# shematic.net
KiCad netlist of a schematic drawn in EAGLE
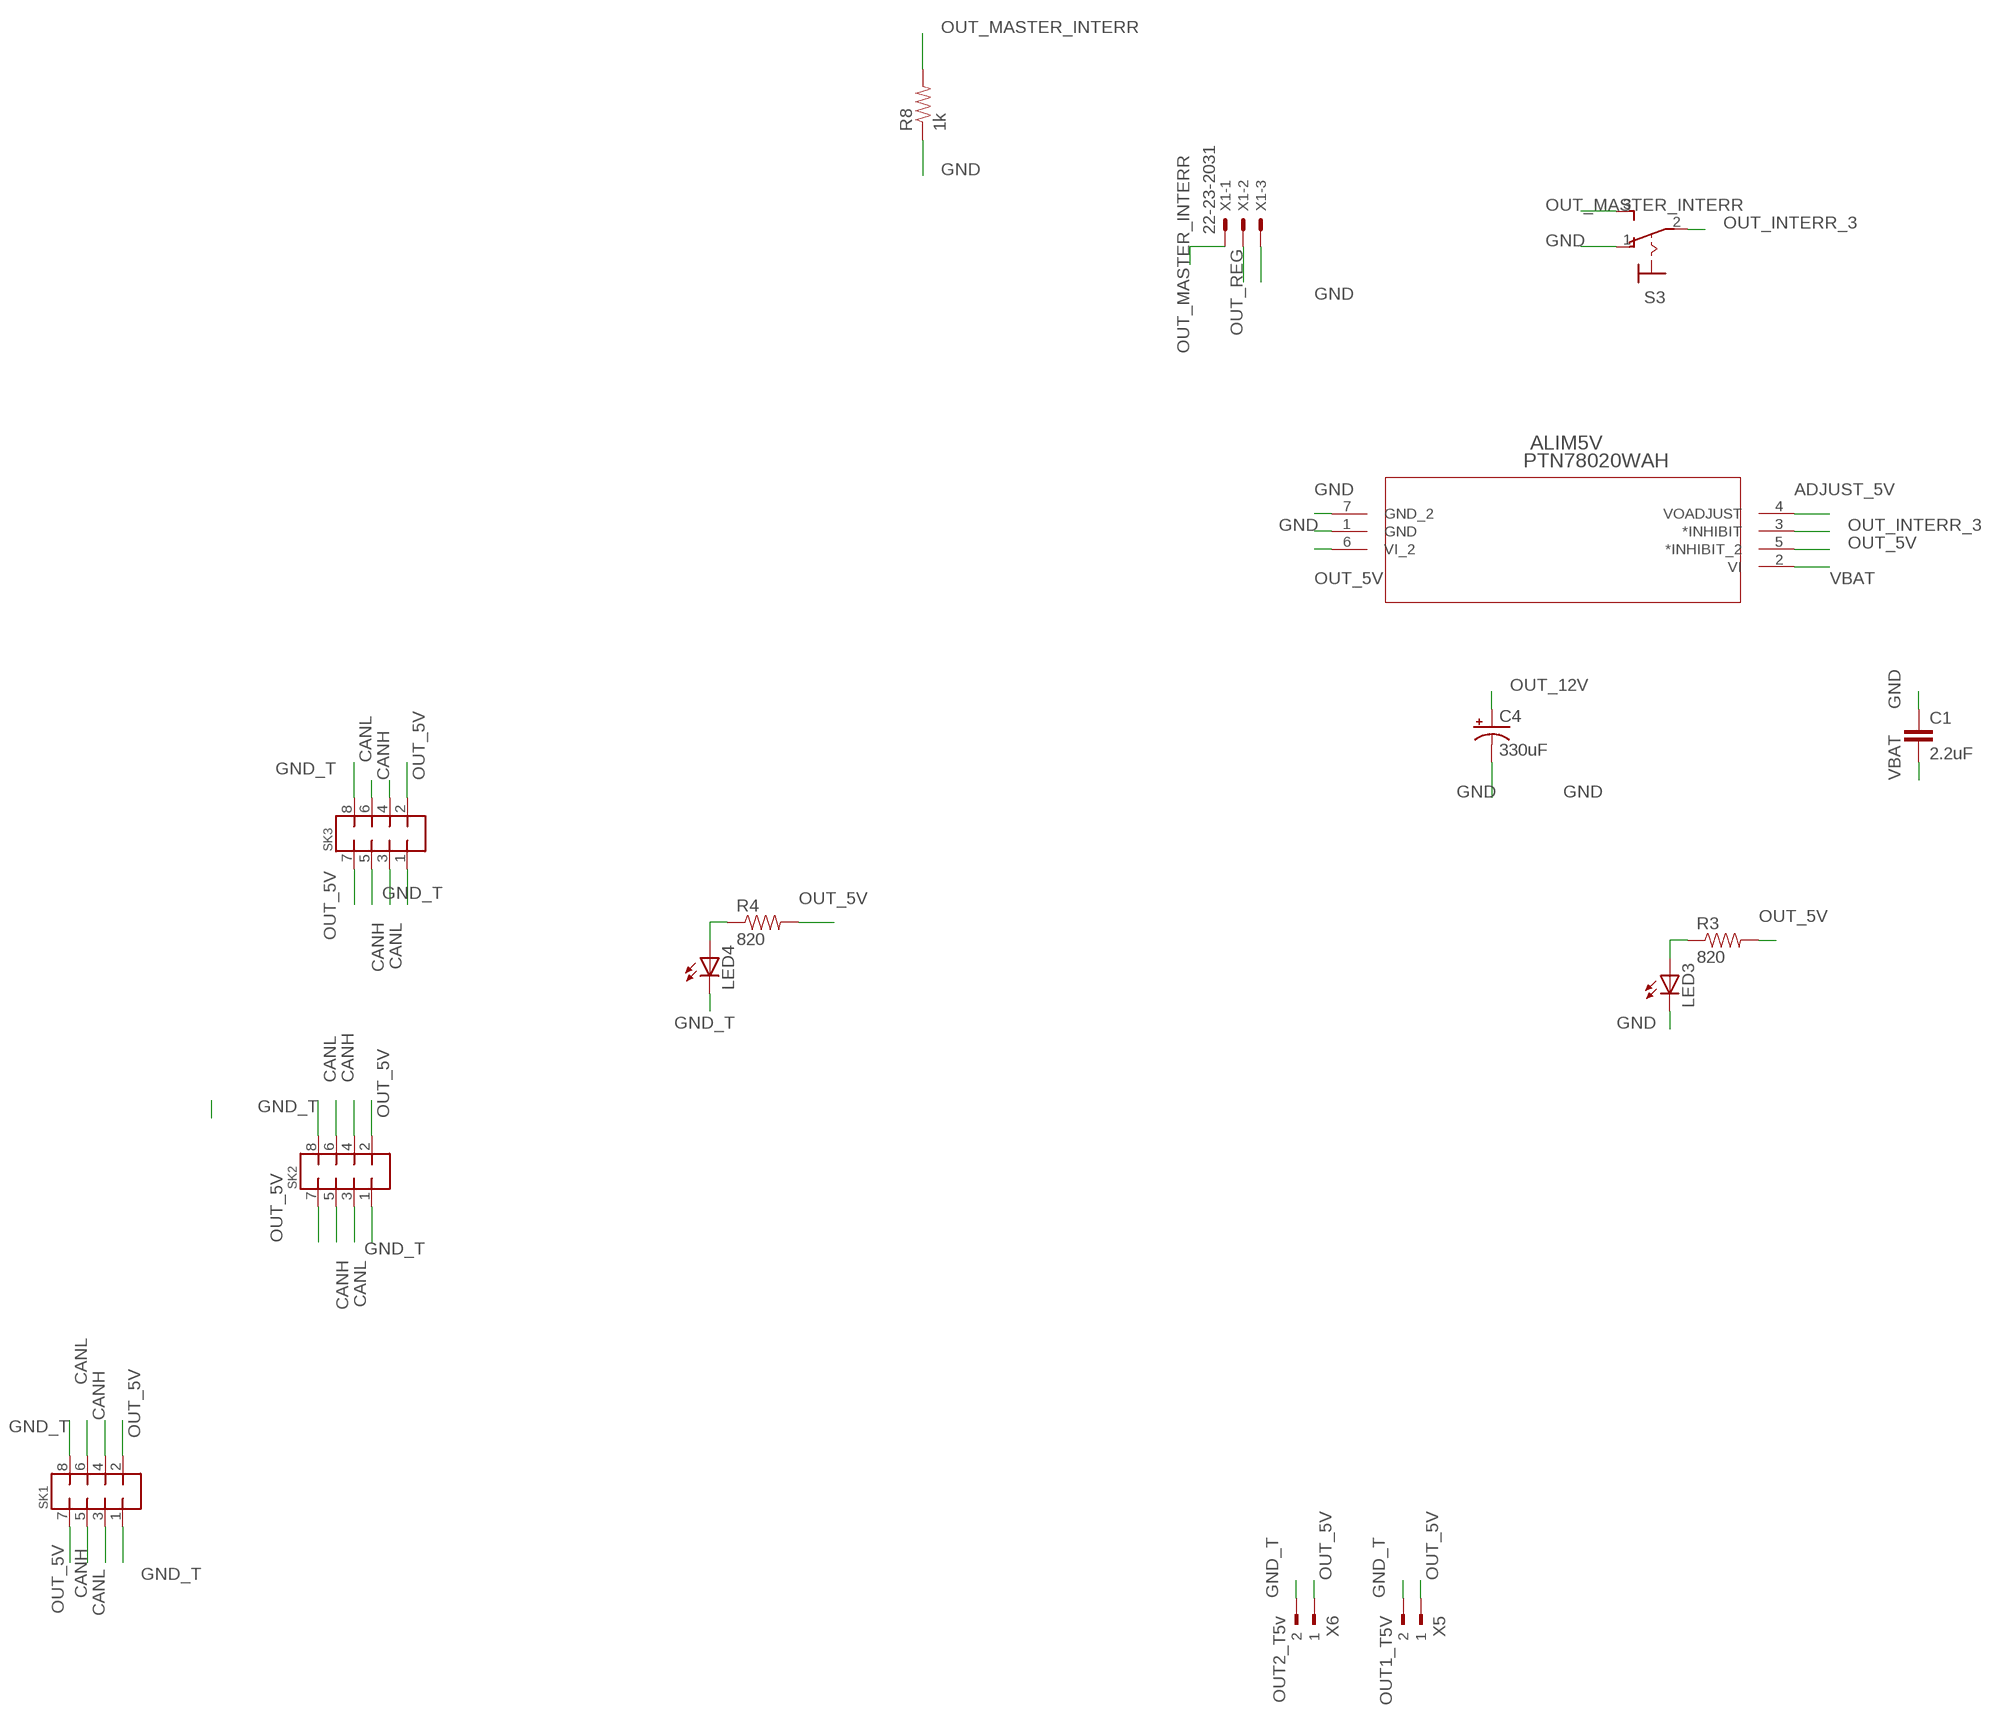
[diagram p0: schematic, sheet 1, part 1 of 2]
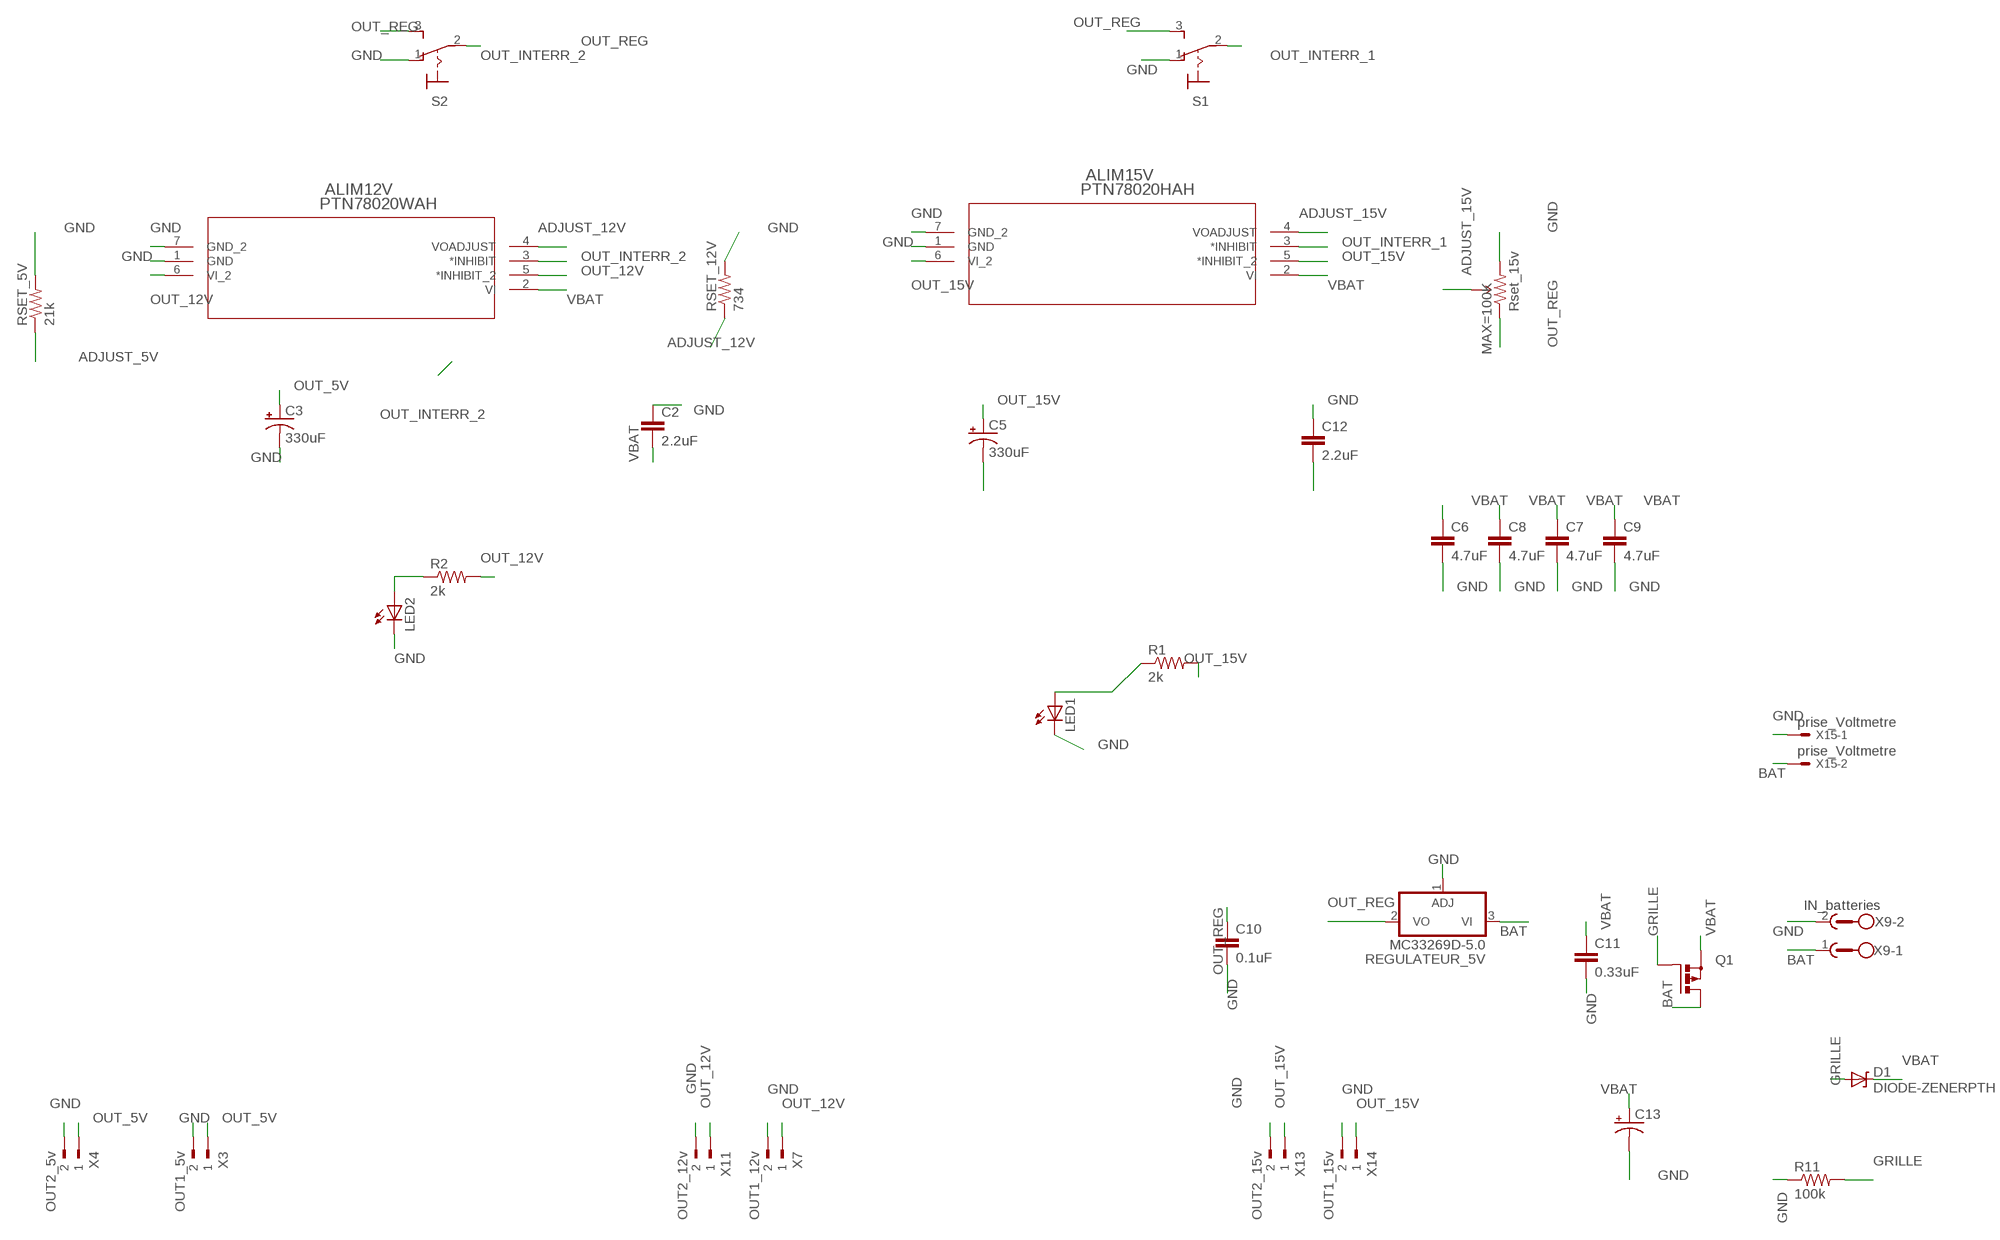
[diagram p1: schematic, sheet 1, part 2 of 2]

(export (version "E")
  (design (tool "Eeschema 10.0.6"))
  (components
    (comp (ref "ALIM5V")
      (value "PTN78020WAH")
      (footprint "eagle-import:EUK7")
      (libsource (lib "eagle-import") (part "PTN78020_"))
    )
    (comp (ref "ALIM12V")
      (value "PTN78020WAH")
      (footprint "eagle-import:EUK7")
      (libsource (lib "eagle-import") (part "PTN78020_"))
    )
    (comp (ref "ALIM15V")
      (value "PTN78020HAH")
      (footprint "eagle-import:EUK7")
      (libsource (lib "eagle-import") (part "PTN78020_"))
    )
    (comp (ref "C1")
      (value "2.2uF")
      (footprint "eagle-import:0805")
      (libsource (lib "eagle-import") (part "CAP0805"))
    )
    (comp (ref "C2")
      (value "2.2uF")
      (footprint "eagle-import:0805")
      (libsource (lib "eagle-import") (part "CAP0805"))
    )
    (comp (ref "C3")
      (value "330uF")
      (footprint "eagle-import:CPOL-RADIAL-100UF-25V")
      (libsource (lib "eagle-import") (part "CAP_POLPTH1"))
    )
    (comp (ref "C4")
      (value "330uF")
      (footprint "eagle-import:CPOL-RADIAL-100UF-25V")
      (libsource (lib "eagle-import") (part "CAP_POLPTH1"))
    )
    (comp (ref "C5")
      (value "330uF")
      (footprint "eagle-import:CPOL-RADIAL-100UF-25V")
      (libsource (lib "eagle-import") (part "CAP_POLPTH1"))
    )
    (comp (ref "C6")
      (value "4.7uF")
      (footprint "eagle-import:0805")
      (libsource (lib "eagle-import") (part "CAP0805"))
    )
    (comp (ref "C7")
      (value "4.7uF")
      (footprint "eagle-import:0805")
      (libsource (lib "eagle-import") (part "CAP0805"))
    )
    (comp (ref "C8")
      (value "4.7uF")
      (footprint "eagle-import:0805")
      (libsource (lib "eagle-import") (part "CAP0805"))
    )
    (comp (ref "C9")
      (value "4.7uF")
      (footprint "eagle-import:0805")
      (libsource (lib "eagle-import") (part "CAP0805"))
    )
    (comp (ref "C10")
      (value "0.1uF")
      (footprint "eagle-import:0805")
      (libsource (lib "eagle-import") (part "CAP0805"))
    )
    (comp (ref "C11")
      (value "0.33uF")
      (footprint "eagle-import:0805")
      (libsource (lib "eagle-import") (part "CAP0805"))
    )
    (comp (ref "C12")
      (value "2.2uF")
      (footprint "eagle-import:0805")
      (libsource (lib "eagle-import") (part "CAP0805"))
    )
    (comp (ref "C13")
      (value "CAP_POLPTH1")
      (footprint "eagle-import:CPOL-RADIAL-100UF-25V")
      (libsource (lib "eagle-import") (part "SparkFun-Passives_CAP_POLPTH1"))
    )
    (comp (ref "D1")
      (value "DIODE-ZENERPTH")
      (footprint "eagle-import:DIODE-ZENER")
      (libsource (lib "eagle-import") (part "DIODE-ZENERPTH"))
    )
    (comp (ref "LED1")
      (value "LEDCHIP-LED0805")
      (footprint "eagle-import:CHIP-LED0805")
      (libsource (lib "eagle-import") (part "LEDCHIP-LED0805"))
    )
    (comp (ref "LED2")
      (value "LEDCHIP-LED0805")
      (footprint "eagle-import:CHIP-LED0805")
      (libsource (lib "eagle-import") (part "LEDCHIP-LED0805"))
    )
    (comp (ref "LED3")
      (value "LEDCHIP-LED0805")
      (footprint "eagle-import:CHIP-LED0805")
      (libsource (lib "eagle-import") (part "LEDCHIP-LED0805"))
    )
    (comp (ref "LED4")
      (value "LEDCHIP-LED0805")
      (footprint "eagle-import:CHIP-LED0805")
      (libsource (lib "eagle-import") (part "LEDCHIP-LED0805"))
    )
    (comp (ref "MAX=100K")
      (value "Rset_15v")
      (footprint "eagle-import:3386U")
      (libsource (lib "eagle-import") (part "TRIMPOT-PTH-KNOB"))
    )
    (comp (ref "Q1")
      (value "PMOSFET_PTO220BH")
      (footprint "eagle-import:TO220BH")
      (libsource (lib "eagle-import") (part "PMOSFET_PTO220BH"))
    )
    (comp (ref "R1")
      (value "2k")
      (footprint "eagle-import:0805")
      (libsource (lib "eagle-import") (part "SparkFun-Resistors_RESISTOR0805-RES"))
    )
    (comp (ref "R2")
      (value "2k")
      (footprint "eagle-import:0805")
      (libsource (lib "eagle-import") (part "SparkFun-Resistors_RESISTOR0805-RES"))
    )
    (comp (ref "R3")
      (value "820")
      (footprint "eagle-import:0805")
      (libsource (lib "eagle-import") (part "SparkFun-Resistors_RESISTOR0805-RES"))
    )
    (comp (ref "R4")
      (value "820")
      (footprint "eagle-import:0805")
      (libsource (lib "eagle-import") (part "SparkFun-Resistors_RESISTOR0805-RES"))
    )
    (comp (ref "R8")
      (value "1k")
      (footprint "eagle-import:0805")
      (libsource (lib "eagle-import") (part "SparkFun-Resistors_RESISTOR0805-RES"))
    )
    (comp (ref "R11")
      (value "100k")
      (footprint "eagle-import:0805")
      (libsource (lib "eagle-import") (part "RESISTOR0805-RES"))
    )
    (comp (ref "REGULATEUR_5V")
      (value "MC33269D-5.0")
      (footprint "eagle-import:DPACK")
      (libsource (lib "eagle-import") (part "MC33269?D-5.0"))
    )
    (comp (ref "RSET_5V")
      (value "21k")
      (footprint "eagle-import:0805")
      (libsource (lib "eagle-import") (part "RESISTOR0805-RES"))
    )
    (comp (ref "RSET_12V")
      (value "734")
      (footprint "eagle-import:0805")
      (libsource (lib "eagle-import") (part "RESISTOR0805-RES"))
    )
    (comp (ref "S1")
      (value "M9040P")
      (footprint "eagle-import:M9040P")
      (libsource (lib "eagle-import") (part "M9040P"))
    )
    (comp (ref "S2")
      (value "M9040P")
      (footprint "eagle-import:M9040P")
      (libsource (lib "eagle-import") (part "M9040P"))
    )
    (comp (ref "S3")
      (value "M9040P")
      (footprint "eagle-import:M9040P")
      (libsource (lib "eagle-import") (part "M9040P"))
    )
    (comp (ref "SK1")
      (value "MMATCH-8-PTH")
      (footprint "eagle-import:AMP-215079-8")
      (libsource (lib "eagle-import") (part "MMATCH-8-PTH"))
    )
    (comp (ref "SK2")
      (value "MMATCH-8-PTH")
      (footprint "eagle-import:AMP-215079-8")
      (libsource (lib "eagle-import") (part "MMATCH-8-PTH"))
    )
    (comp (ref "SK3")
      (value "MMATCH-8-PTH")
      (footprint "eagle-import:AMP-215079-8")
      (libsource (lib "eagle-import") (part "MMATCH-8-PTH"))
    )
    (comp (ref "X1")
      (value "22-23-2031")
      (footprint "eagle-import:22-23-2031")
      (fields (field (name "MF") "MOLEX"))
      (libsource (lib "eagle-import") (part "22-23-2031"))
    )
    (comp (ref "X3")
      (value "OUT1_5v")
      (footprint "eagle-import:90-2")
      (libsource (lib "eagle-import") (part "90-2"))
    )
    (comp (ref "X4")
      (value "OUT2_5v")
      (footprint "eagle-import:90-2")
      (libsource (lib "eagle-import") (part "90-2"))
    )
    (comp (ref "X5")
      (value "OUT1_T5V")
      (footprint "eagle-import:90-2")
      (libsource (lib "eagle-import") (part "90-2"))
    )
    (comp (ref "X6")
      (value "OUT2_T5v")
      (footprint "eagle-import:90-2")
      (libsource (lib "eagle-import") (part "90-2"))
    )
    (comp (ref "X7")
      (value "OUT1_12v")
      (footprint "eagle-import:90-2")
      (libsource (lib "eagle-import") (part "90-2"))
    )
    (comp (ref "X9")
      (value "IN_batteries")
      (footprint "eagle-import:GMSTBA2")
      (fields (field (name "MF") "FARNELL") (field (name "MPN") "1757242"))
      (libsource (lib "eagle-import") (part "GMSTBA2"))
    )
    (comp (ref "X11")
      (value "OUT2_12v")
      (footprint "eagle-import:90-2")
      (libsource (lib "eagle-import") (part "90-2"))
    )
    (comp (ref "X13")
      (value "OUT2_15v")
      (footprint "eagle-import:90-2")
      (libsource (lib "eagle-import") (part "90-2"))
    )
    (comp (ref "X14")
      (value "OUT1_15v")
      (footprint "eagle-import:90-2")
      (libsource (lib "eagle-import") (part "90-2"))
    )
    (comp (ref "X15")
      (value "prise_Voltmetre")
      (footprint "eagle-import:KK-156-2")
      (libsource (lib "eagle-import") (part "KK-156-2"))
    )
  )
  (nets
    (net (code "1") (name "/ADJUST_5V") (class "Default")
      (node (ref "ALIM5V") (pin "4") (pinfunction "VOADJUST_4") (pintype "passive"))
      (node (ref "RSET_5V") (pin "1") (pinfunction "1_1") (pintype "passive"))
    )
    (net (code "2") (name "/ADJUST_12V") (class "Default")
      (node (ref "ALIM12V") (pin "4") (pinfunction "VOADJUST_4") (pintype "passive"))
      (node (ref "RSET_12V") (pin "1") (pinfunction "1_1") (pintype "passive"))
    )
    (net (code "3") (name "/ADJUST_15V") (class "Default")
      (node (ref "ALIM15V") (pin "4") (pinfunction "VOADJUST_4") (pintype "passive"))
      (node (ref "MAX=100K") (pin "2") (pinfunction "WIPER_2") (pintype "passive"))
    )
    (net (code "4") (name "/BAT") (class "Default")
      (node (ref "Q1") (pin "D") (pinfunction "D_D") (pintype "passive"))
      (node (ref "REGULATEUR_5V") (pin "3") (pinfunction "VI_3") (pintype "input"))
      (node (ref "X15") (pin "2") (pinfunction "S_2") (pintype "passive"))
      (node (ref "X9") (pin "1") (pinfunction "1_1") (pintype "passive"))
    )
    (net (code "5") (name "/CANH") (class "Default")
      (node (ref "SK1") (pin "4") (pinfunction "4_4") (pintype "bidirectional"))
      (node (ref "SK1") (pin "5") (pinfunction "5_5") (pintype "bidirectional"))
      (node (ref "SK2") (pin "4") (pinfunction "4_4") (pintype "bidirectional"))
      (node (ref "SK2") (pin "5") (pinfunction "5_5") (pintype "bidirectional"))
      (node (ref "SK3") (pin "4") (pinfunction "4_4") (pintype "bidirectional"))
      (node (ref "SK3") (pin "5") (pinfunction "5_5") (pintype "bidirectional"))
    )
    (net (code "6") (name "/CANL") (class "Default")
      (node (ref "SK1") (pin "3") (pinfunction "3_3") (pintype "bidirectional"))
      (node (ref "SK1") (pin "6") (pinfunction "6_6") (pintype "bidirectional"))
      (node (ref "SK2") (pin "3") (pinfunction "3_3") (pintype "bidirectional"))
      (node (ref "SK2") (pin "6") (pinfunction "6_6") (pintype "bidirectional"))
      (node (ref "SK3") (pin "3") (pinfunction "3_3") (pintype "bidirectional"))
      (node (ref "SK3") (pin "6") (pinfunction "6_6") (pintype "bidirectional"))
    )
    (net (code "7") (name "/GND") (class "Default")
      (node (ref "ALIM12V") (pin "1") (pinfunction "GND_1") (pintype "passive"))
      (node (ref "ALIM12V") (pin "7") (pinfunction "GND_2_7") (pintype "passive"))
      (node (ref "ALIM15V") (pin "1") (pinfunction "GND_1") (pintype "passive"))
      (node (ref "ALIM15V") (pin "7") (pinfunction "GND_2_7") (pintype "passive"))
      (node (ref "ALIM5V") (pin "1") (pinfunction "GND_1") (pintype "passive"))
      (node (ref "ALIM5V") (pin "7") (pinfunction "GND_2_7") (pintype "passive"))
      (node (ref "C1") (pin "1") (pinfunction "1_1") (pintype "passive"))
      (node (ref "C10") (pin "2") (pinfunction "2_2") (pintype "passive"))
      (node (ref "C11") (pin "2") (pinfunction "2_2") (pintype "passive"))
      (node (ref "C12") (pin "1") (pinfunction "1_1") (pintype "passive"))
      (node (ref "C13") (pin "2") (pinfunction "-_2") (pintype "passive"))
      (node (ref "C2") (pin "1") (pinfunction "1_1") (pintype "passive"))
      (node (ref "C3") (pin "2") (pinfunction "-_2") (pintype "passive"))
      (node (ref "C4") (pin "2") (pinfunction "-_2") (pintype "passive"))
      (node (ref "C5") (pin "2") (pinfunction "-_2") (pintype "passive"))
      (node (ref "C6") (pin "2") (pinfunction "2_2") (pintype "passive"))
      (node (ref "C7") (pin "2") (pinfunction "2_2") (pintype "passive"))
      (node (ref "C8") (pin "2") (pinfunction "2_2") (pintype "passive"))
      (node (ref "C9") (pin "2") (pinfunction "2_2") (pintype "passive"))
      (node (ref "LED1") (pin "C") (pinfunction "C_C") (pintype "passive"))
      (node (ref "LED2") (pin "C") (pinfunction "C_C") (pintype "passive"))
      (node (ref "LED3") (pin "C") (pinfunction "C_C") (pintype "passive"))
      (node (ref "MAX=100K") (pin "3") (pinfunction "CW_3") (pintype "passive"))
      (node (ref "R11") (pin "1") (pinfunction "1_1") (pintype "passive"))
      (node (ref "R8") (pin "1") (pinfunction "1_1") (pintype "passive"))
      (node (ref "REGULATEUR_5V") (pin "1") (pinfunction "ADJ_1") (pintype "input"))
      (node (ref "RSET_12V") (pin "2") (pinfunction "2_2") (pintype "passive"))
      (node (ref "RSET_5V") (pin "2") (pinfunction "2_2") (pintype "passive"))
      (node (ref "S1") (pin "1") (pinfunction "O_1") (pintype "passive"))
      (node (ref "S2") (pin "1") (pinfunction "O_1") (pintype "passive"))
      (node (ref "S3") (pin "1") (pinfunction "O_1") (pintype "passive"))
      (node (ref "X1") (pin "3") (pinfunction "S_3") (pintype "passive"))
      (node (ref "X11") (pin "2") (pinfunction "2_2") (pintype "passive"))
      (node (ref "X13") (pin "2") (pinfunction "2_2") (pintype "passive"))
      (node (ref "X14") (pin "2") (pinfunction "2_2") (pintype "passive"))
      (node (ref "X15") (pin "1") (pinfunction "S_1") (pintype "passive"))
      (node (ref "X3") (pin "2") (pinfunction "2_2") (pintype "passive"))
      (node (ref "X4") (pin "2") (pinfunction "2_2") (pintype "passive"))
      (node (ref "X7") (pin "2") (pinfunction "2_2") (pintype "passive"))
      (node (ref "X9") (pin "2") (pinfunction "1_2") (pintype "passive"))
    )
    (net (code "8") (name "/GND_T") (class "Default")
      (node (ref "LED4") (pin "C") (pinfunction "C_C") (pintype "passive"))
      (node (ref "SK1") (pin "1") (pinfunction "1_1") (pintype "bidirectional"))
      (node (ref "SK1") (pin "8") (pinfunction "8_8") (pintype "bidirectional"))
      (node (ref "SK2") (pin "1") (pinfunction "1_1") (pintype "bidirectional"))
      (node (ref "SK2") (pin "8") (pinfunction "8_8") (pintype "bidirectional"))
      (node (ref "SK3") (pin "1") (pinfunction "1_1") (pintype "bidirectional"))
      (node (ref "SK3") (pin "8") (pinfunction "8_8") (pintype "bidirectional"))
      (node (ref "X5") (pin "2") (pinfunction "2_2") (pintype "passive"))
      (node (ref "X6") (pin "2") (pinfunction "2_2") (pintype "passive"))
    )
    (net (code "9") (name "/GRILLE") (class "Default")
      (node (ref "D1") (pin "P$2") (pinfunction "A_P$2") (pintype "passive"))
      (node (ref "Q1") (pin "G") (pinfunction "G_G") (pintype "passive"))
      (node (ref "R11") (pin "2") (pinfunction "2_2") (pintype "passive"))
    )
    (net (code "10") (name "/OUT_5V") (class "Default")
      (node (ref "ALIM5V") (pin "5") (pinfunction "*INHIBIT_2_5") (pintype "passive"))
      (node (ref "ALIM5V") (pin "6") (pinfunction "VI_2_6") (pintype "passive"))
      (node (ref "C3") (pin "1") (pinfunction "+_1") (pintype "passive"))
      (node (ref "R3") (pin "2") (pinfunction "2_2") (pintype "passive"))
      (node (ref "R4") (pin "2") (pinfunction "2_2") (pintype "passive"))
      (node (ref "SK1") (pin "2") (pinfunction "2_2") (pintype "bidirectional"))
      (node (ref "SK1") (pin "7") (pinfunction "7_7") (pintype "bidirectional"))
      (node (ref "SK2") (pin "2") (pinfunction "2_2") (pintype "bidirectional"))
      (node (ref "SK2") (pin "7") (pinfunction "7_7") (pintype "bidirectional"))
      (node (ref "SK3") (pin "2") (pinfunction "2_2") (pintype "bidirectional"))
      (node (ref "SK3") (pin "7") (pinfunction "7_7") (pintype "bidirectional"))
      (node (ref "X3") (pin "1") (pinfunction "1_1") (pintype "passive"))
      (node (ref "X4") (pin "1") (pinfunction "1_1") (pintype "passive"))
      (node (ref "X5") (pin "1") (pinfunction "1_1") (pintype "passive"))
      (node (ref "X6") (pin "1") (pinfunction "1_1") (pintype "passive"))
    )
    (net (code "11") (name "/OUT_12V") (class "Default")
      (node (ref "ALIM12V") (pin "5") (pinfunction "*INHIBIT_2_5") (pintype "passive"))
      (node (ref "ALIM12V") (pin "6") (pinfunction "VI_2_6") (pintype "passive"))
      (node (ref "C4") (pin "1") (pinfunction "+_1") (pintype "passive"))
      (node (ref "R2") (pin "2") (pinfunction "2_2") (pintype "passive"))
      (node (ref "X11") (pin "1") (pinfunction "1_1") (pintype "passive"))
      (node (ref "X7") (pin "1") (pinfunction "1_1") (pintype "passive"))
    )
    (net (code "12") (name "/OUT_15V") (class "Default")
      (node (ref "ALIM15V") (pin "5") (pinfunction "*INHIBIT_2_5") (pintype "passive"))
      (node (ref "ALIM15V") (pin "6") (pinfunction "VI_2_6") (pintype "passive"))
      (node (ref "C5") (pin "1") (pinfunction "+_1") (pintype "passive"))
      (node (ref "R1") (pin "2") (pinfunction "2_2") (pintype "passive"))
      (node (ref "X13") (pin "1") (pinfunction "1_1") (pintype "passive"))
      (node (ref "X14") (pin "1") (pinfunction "1_1") (pintype "passive"))
    )
    (net (code "13") (name "/OUT_INTERR_1") (class "Default")
      (node (ref "ALIM15V") (pin "3") (pinfunction "*INHIBIT_3") (pintype "passive"))
      (node (ref "S1") (pin "2") (pinfunction "P_2") (pintype "passive"))
    )
    (net (code "14") (name "/OUT_INTERR_2") (class "Default")
      (node (ref "ALIM12V") (pin "3") (pinfunction "*INHIBIT_3") (pintype "passive"))
      (node (ref "S2") (pin "2") (pinfunction "P_2") (pintype "passive"))
    )
    (net (code "15") (name "/OUT_INTERR_3") (class "Default")
      (node (ref "ALIM5V") (pin "3") (pinfunction "*INHIBIT_3") (pintype "passive"))
      (node (ref "S3") (pin "2") (pinfunction "P_2") (pintype "passive"))
    )
    (net (code "16") (name "/OUT_MASTER_INTERR") (class "Default")
      (node (ref "R8") (pin "2") (pinfunction "2_2") (pintype "passive"))
      (node (ref "S3") (pin "3") (pinfunction "S_3") (pintype "passive"))
      (node (ref "X1") (pin "1") (pinfunction "S_1") (pintype "passive"))
    )
    (net (code "17") (name "/OUT_REG") (class "Default")
      (node (ref "C10") (pin "1") (pinfunction "1_1") (pintype "passive"))
      (node (ref "MAX=100K") (pin "1") (pinfunction "CCW_1") (pintype "passive"))
      (node (ref "REGULATEUR_5V") (pin "2") (pinfunction "VO_2") (pintype "passive"))
      (node (ref "S1") (pin "3") (pinfunction "S_3") (pintype "passive"))
      (node (ref "S2") (pin "3") (pinfunction "S_3") (pintype "passive"))
      (node (ref "X1") (pin "2") (pinfunction "S_2") (pintype "passive"))
    )
    (net (code "18") (name "/VBAT") (class "Default")
      (node (ref "ALIM12V") (pin "2") (pinfunction "VI_2") (pintype "passive"))
      (node (ref "ALIM15V") (pin "2") (pinfunction "VI_2") (pintype "passive"))
      (node (ref "ALIM5V") (pin "2") (pinfunction "VI_2") (pintype "passive"))
      (node (ref "C1") (pin "2") (pinfunction "2_2") (pintype "passive"))
      (node (ref "C11") (pin "1") (pinfunction "1_1") (pintype "passive"))
      (node (ref "C12") (pin "2") (pinfunction "2_2") (pintype "passive"))
      (node (ref "C13") (pin "1") (pinfunction "+_1") (pintype "passive"))
      (node (ref "C2") (pin "2") (pinfunction "2_2") (pintype "passive"))
      (node (ref "C6") (pin "1") (pinfunction "1_1") (pintype "passive"))
      (node (ref "C7") (pin "1") (pinfunction "1_1") (pintype "passive"))
      (node (ref "C8") (pin "1") (pinfunction "1_1") (pintype "passive"))
      (node (ref "C9") (pin "1") (pinfunction "1_1") (pintype "passive"))
      (node (ref "D1") (pin "P$1") (pinfunction "C_P$1") (pintype "passive"))
      (node (ref "Q1") (pin "S") (pinfunction "S_S") (pintype "passive"))
    )
    (net (code "19") (name "Net-(LED1-PadA)") (class "Default")
      (node (ref "LED1") (pin "A") (pinfunction "A_A") (pintype "passive"))
      (node (ref "R1") (pin "1") (pinfunction "1_1") (pintype "passive"))
    )
    (net (code "20") (name "Net-(LED2-PadA)") (class "Default")
      (node (ref "LED2") (pin "A") (pinfunction "A_A") (pintype "passive"))
      (node (ref "R2") (pin "1") (pinfunction "1_1") (pintype "passive"))
    )
    (net (code "21") (name "Net-(LED3-PadA)") (class "Default")
      (node (ref "LED3") (pin "A") (pinfunction "A_A") (pintype "passive"))
      (node (ref "R3") (pin "1") (pinfunction "1_1") (pintype "passive"))
    )
    (net (code "22") (name "Net-(LED4-PadA)") (class "Default")
      (node (ref "LED4") (pin "A") (pinfunction "A_A") (pintype "passive"))
      (node (ref "R4") (pin "1") (pinfunction "1_1") (pintype "passive"))
    )
  )
)
